# MiddleMotor.net
KiCad netlist of a schematic drawn in EasyEDA Pro
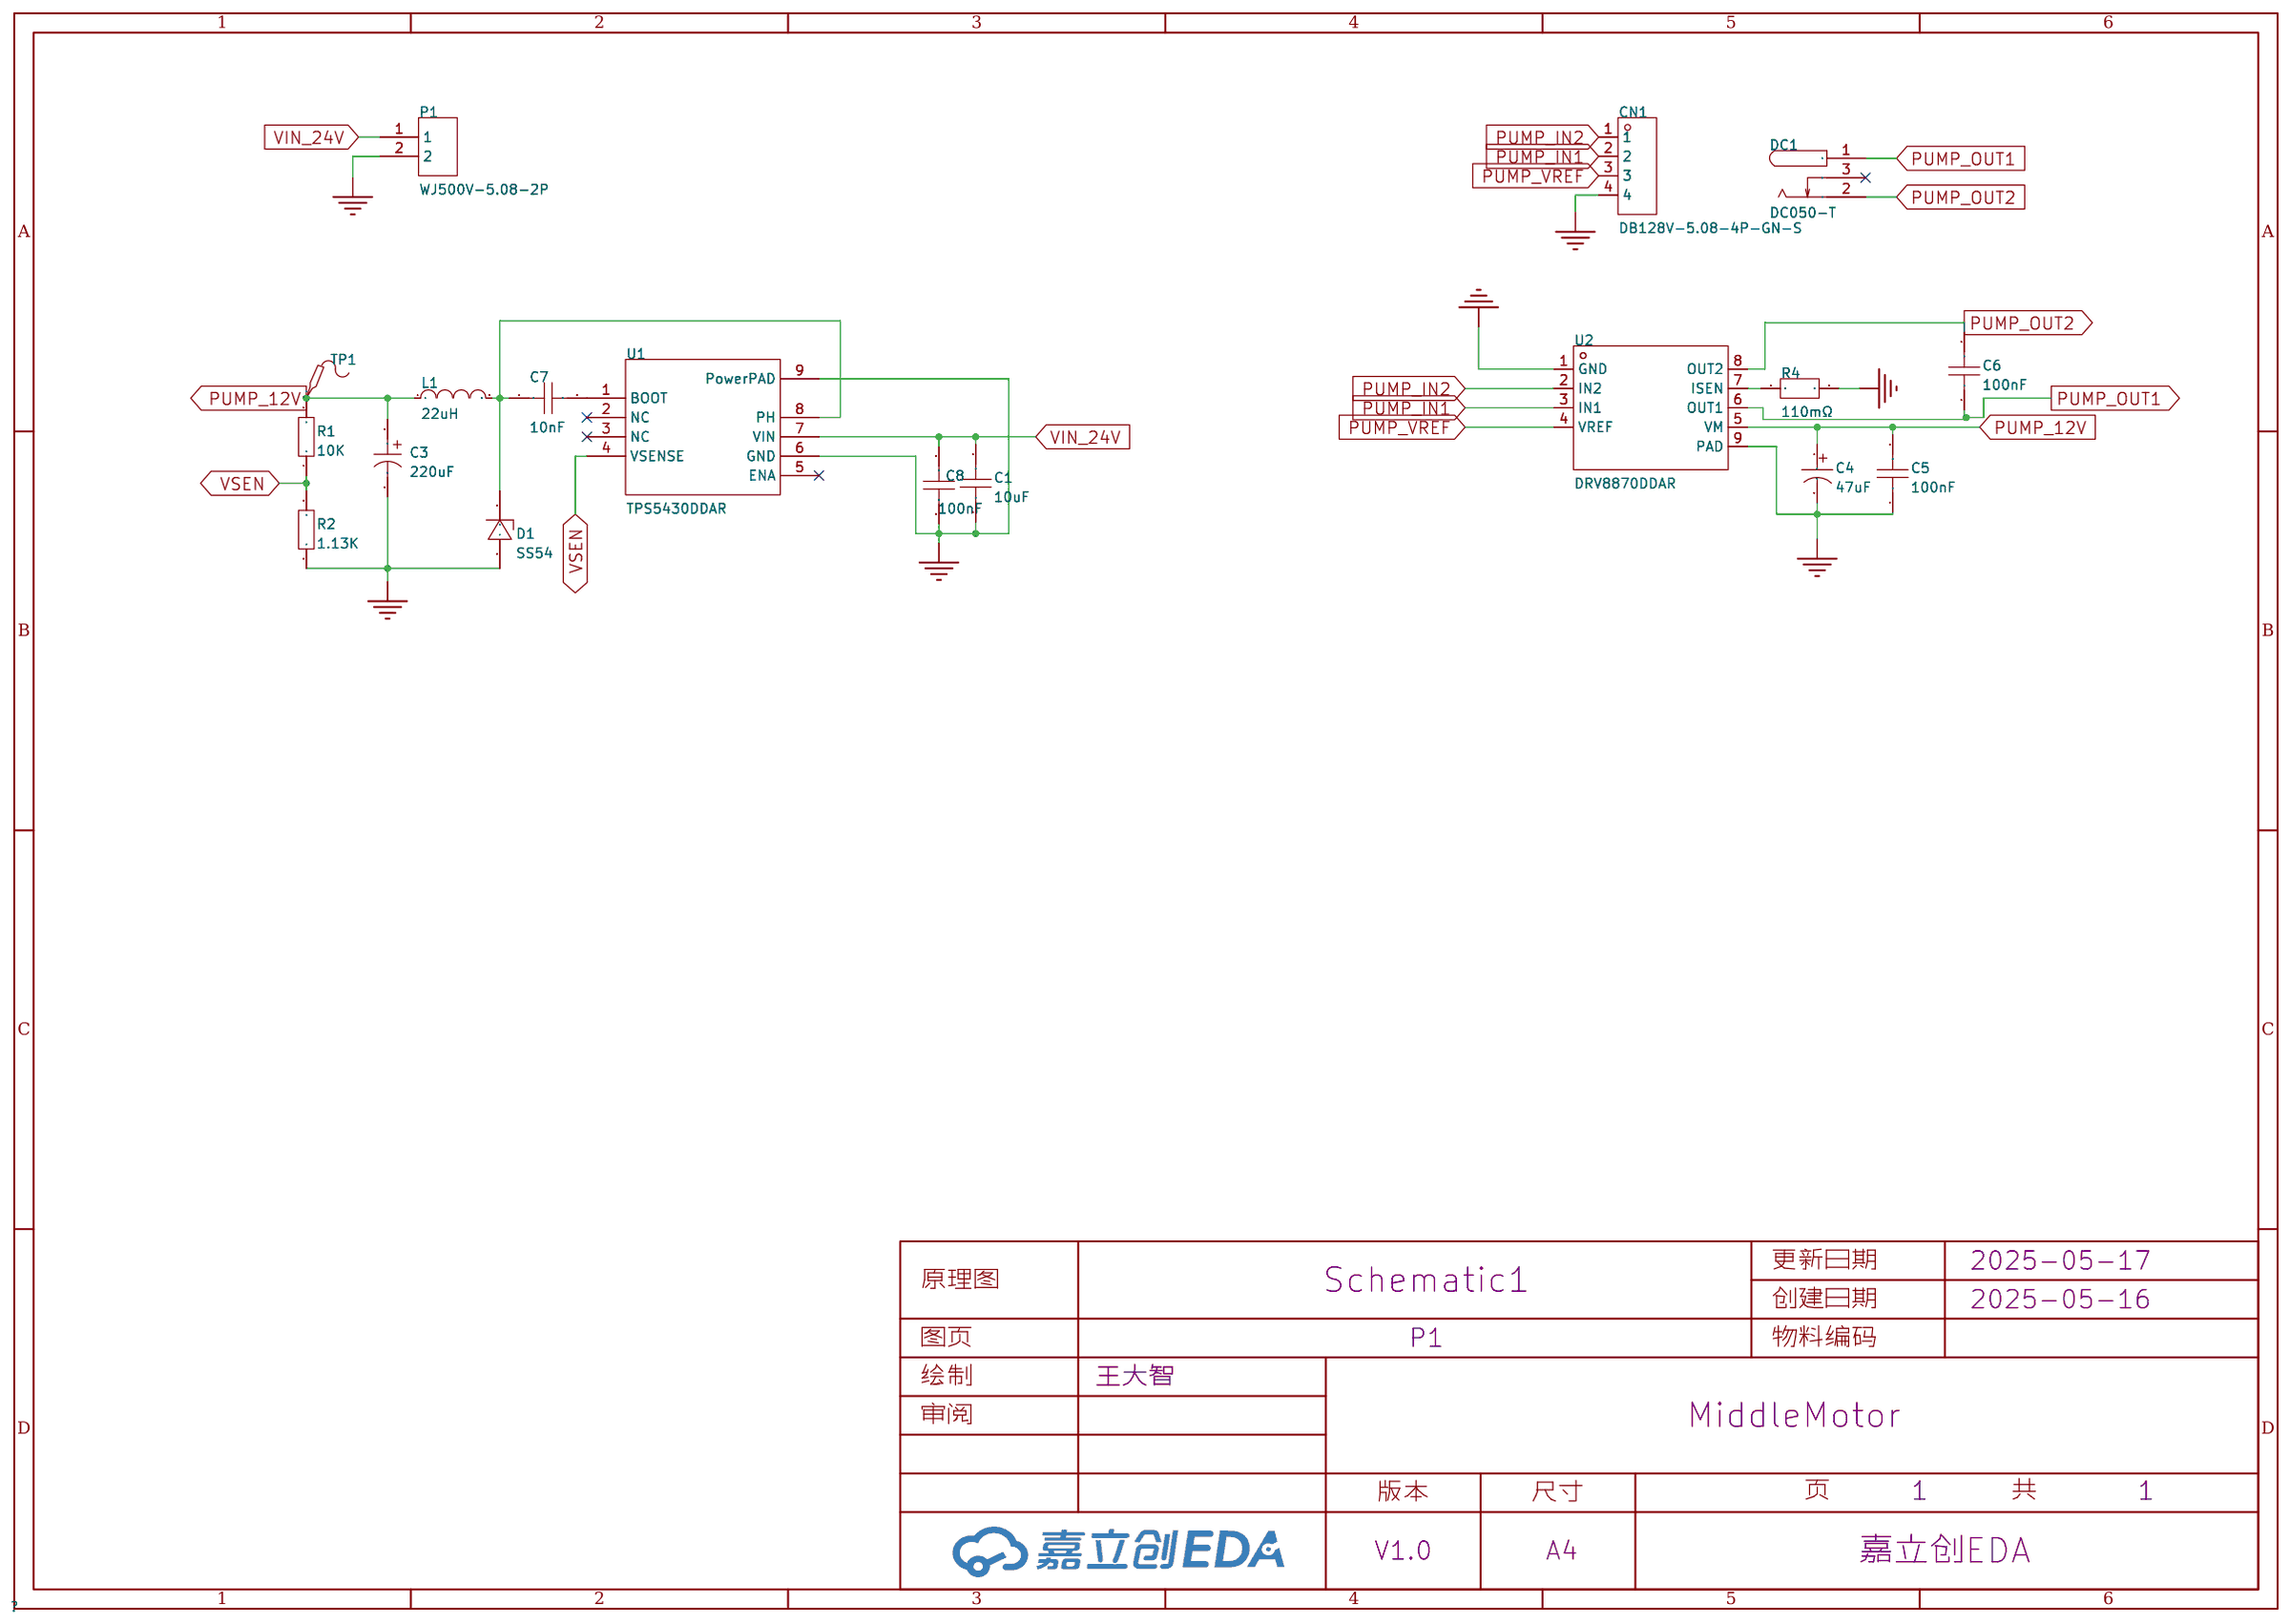
[diagram p0: schematic sheet]

(export (version "E")
  (design (tool "Eeschema 10.0.6"))
  (components
    (comp (ref "C1")
      (value "10uF")
      (footprint "easyedapro:C1206")
      (description "容值:10uF;精度:±10%;额定电压:50V;温度系数:X5R;")
      (fields
        (field (name "Manufacturer Part") "HGC1206R5106K500NSPJ")
        (field (name "Manufacturer") "Chinocera(华瓷)")
      )
      (libsource (lib "easyedapro") (part "HGC1206R5106K500NSPJ"))
    )
    (comp (ref "C3")
      (value "220uF")
      (footprint "easyedapro:CAP-SMD_BD8.0-L8.3-W8.3-FD")
      (description "容值:220uF;精度:±20%;额定电压:35V;纹波电流:175mA@120Hz;")
      (fields
        (field (name "Manufacturer Part") "GVT1V227M0810CNVC")
        (field (name "Manufacturer") "HRK(鸿瑞凯电子)")
      )
      (libsource (lib "easyedapro") (part "GVT1V227M0810CNVC"))
    )
    (comp (ref "C4")
      (value "47uF")
      (footprint "easyedapro:CAP-TH_BD6.3-P2.50-D1.0-FD")
      (description "容值:47uF;精度:±20%;额定电压:50V;")
      (fields
        (field (name "Manufacturer Part") "KM476M050E11RR0VH2FP0")
        (field (name "Manufacturer") "CX(承兴)")
      )
      (libsource (lib "easyedapro") (part "47uF 50V 6.3*11_C45101"))
    )
    (comp (ref "C5")
      (value "100nF")
      (footprint "easyedapro:C0603")
      (description "容值:100nF;精度:±10%;额定电压:50V;温度系数:X7R;")
      (fields
        (field (name "Manufacturer Part") "CGA0603X7R104K500JT")
        (field (name "Manufacturer") "HRE(芯声)")
      )
      (libsource (lib "easyedapro") (part "CGA0603X7R104K500JT"))
    )
    (comp (ref "C6")
      (value "100nF")
      (footprint "easyedapro:C0603")
      (description "容值:100nF;精度:±10%;额定电压:50V;温度系数:X7R;")
      (fields
        (field (name "Manufacturer Part") "CGA0603X7R104K500JT")
        (field (name "Manufacturer") "HRE(芯声)")
      )
      (libsource (lib "easyedapro") (part "CGA0603X7R104K500JT"))
    )
    (comp (ref "C7")
      (value "10nF")
      (footprint "easyedapro:C0603")
      (libsource (lib "easyedapro") (part "CapAcitance"))
    )
    (comp (ref "C8")
      (value "100nF")
      (footprint "easyedapro:C0603")
      (libsource (lib "easyedapro") (part "CapAcitance"))
    )
    (comp (ref "CN1")
      (value "DB128V-5.08-4P-GN-S")
      (footprint "easyedapro:CONN-TH_4P-P5.08_DIBO_DB128V-5.08")
      (fields (field (name "Manufacturer") "DORABO(地博电气)"))
      (libsource (lib "easyedapro") (part "DB128V-5.08-4P-GN-S"))
    )
    (comp (ref "D1")
      (value "SS54")
      (footprint "easyedapro:SMA_L4.3-W2.6-LS5.0-FD")
      (description "二极管配置:独立式;正向压降(Vf):550mV@5.0A;直流反向耐压(Vr):40V;整流电流:5A;")
      (fields (field (name "Manufacturer") "宏迦橙"))
      (libsource (lib "easyedapro") (part "SS54_C7420369"))
    )
    (comp (ref "DC1")
      (value "DC050-T")
      (footprint "easyedapro:DC-IN_DC050-T")
      (description "连接器类型:DC电源插座;安装方式:卧贴;触点内径:2mm;触点外径:6.4mm;额定电流:2A;额定电压:30V;工作温度范围:-25°C~+70°C;")
      (fields (field (name "Manufacturer") "SHOU HAN(首韩)"))
      (libsource (lib "easyedapro") (part "DC050-T"))
    )
    (comp (ref "L1")
      (value "22uH")
      (footprint "easyedapro:IND-SMD_L7.0-W6.6_FXL0630")
      (description "电感值:22uH;精度:±20%;额定电流:2.5A;饱和电流(Isat):3A;类型:一体成型电感;")
      (fields (field (name "Manufacturer Part") "FXL0630-220-M") (field (name "Manufacturer") "cjiang(长江微电)"))
      (libsource (lib "easyedapro") (part "FXL0630-220-M"))
    )
    (comp (ref "P1")
      (value "WJ500V-5.08-2P")
      (footprint "easyedapro:CONN-TH_2P-P5.00_WJ500V-5.08-2P")
      (fields (field (name "Manufacturer") "KANGNEX(康奈克斯电气)"))
      (libsource (lib "easyedapro") (part "WJ500V-5.08-2P-14-00A"))
    )
    (comp (ref "R1") (value "10K") (footprint "easyedapro:R0603") (libsource (lib "easyedapro") (part "电阻")))
    (comp (ref "R2")
      (value "1.13K")
      (footprint "easyedapro:R0603")
      (libsource (lib "easyedapro") (part "电阻"))
    )
    (comp (ref "R4")
      (value "110mΩ")
      (footprint "easyedapro:R1206")
      (description "电阻类型:厚膜电阻;阻值:110mΩ;精度:±1%;功率:250mW;最大工作电压:500V;温度系数:±600ppm/°C;")
      (fields (field (name "Manufacturer Part") "FRL1206FR110TS") (field (name "Manufacturer") "FOJAN(富捷)"))
      (libsource (lib "easyedapro") (part "FRL1206FR110TS"))
    )
    (comp (ref "TP1")
      (value "~")
      (footprint "easyedapro:Test-Point-0.5mm")
      (description "Test Point 测试点")
      (libsource (lib "easyedapro") (part "Test-Point"))
    )
    (comp (ref "U1")
      (value "TPS5430DDAR")
      (footprint "easyedapro:ESOP-8_L4.9-W3.9-P1.27-LS6.0-TL-EP")
      (description "功能类型:降压型;输出类型:可调;工作电压:5.5V~36V;输出电压:1.221V~32.04V;输出电流:3A;")
      (fields (field (name "Manufacturer") "TI(德州仪器)"))
      (libsource (lib "easyedapro") (part "TPS5430DDAR"))
    )
    (comp (ref "U2")
      (value "DRV8870DDAR")
      (footprint "easyedapro:HSOP-8_L5.0-W4.0-P1.27-LS6.2-BL-EP")
      (description "DRV8870 具有电流调节功能的 50V、3.6A、H 桥电机驱动器")
      (fields (field (name "Manufacturer") "TI(德州仪器)"))
      (libsource (lib "easyedapro") (part "DRV8870DDAR"))
    )
  )
  (nets
    (net (code "1") (name "GND") (class "Default")
      (node (ref "C1") (pin "1") (pinfunction "1_1") (pintype "unspecified"))
      (node (ref "C3") (pin "2") (pinfunction "2_2") (pintype "input"))
      (node (ref "C4") (pin "2") (pinfunction "2_2") (pintype "input"))
      (node (ref "C5") (pin "1") (pinfunction "1_1") (pintype "unspecified"))
      (node (ref "C8") (pin "2") (pinfunction "2_2") (pintype "input"))
      (node (ref "CN1") (pin "4") (pinfunction "4_4") (pintype "unspecified"))
      (node (ref "D1") (pin "1") (pinfunction "A_1") (pintype "unspecified"))
      (node (ref "P1") (pin "2") (pinfunction "2_2") (pintype "unspecified"))
      (node (ref "R2") (pin "1") (pinfunction "1_1") (pintype "input"))
      (node (ref "R4") (pin "2") (pinfunction "2_2") (pintype "unspecified"))
      (node (ref "U1") (pin "6") (pinfunction "GND_6") (pintype "unspecified"))
      (node (ref "U1") (pin "9") (pinfunction "PowerPAD_9") (pintype "unspecified"))
      (node (ref "U2") (pin "1") (pinfunction "GND_1") (pintype "unspecified"))
      (node (ref "U2") (pin "9") (pinfunction "PAD_9") (pintype "unspecified"))
    )
    (net (code "2") (name "Net-(D1-K)") (class "Default")
      (node (ref "C7") (pin "1") (pinfunction "1_1") (pintype "input"))
      (node (ref "D1") (pin "2") (pinfunction "K_2") (pintype "unspecified"))
      (node (ref "L1") (pin "2") (pinfunction "2_2") (pintype "unspecified"))
      (node (ref "U1") (pin "8") (pinfunction "PH_8") (pintype "unspecified"))
    )
    (net (code "3") (name "Net-(U1-BOOT)") (class "Default")
      (node (ref "C7") (pin "2") (pinfunction "2_2") (pintype "input"))
      (node (ref "U1") (pin "1") (pinfunction "BOOT_1") (pintype "unspecified"))
    )
    (net (code "4") (name "Net-(U2-ISEN)") (class "Default")
      (node (ref "R4") (pin "1") (pinfunction "1_1") (pintype "unspecified"))
      (node (ref "U2") (pin "7") (pinfunction "ISEN_7") (pintype "unspecified"))
    )
    (net (code "5") (name "PUMP_12V") (class "Default")
      (node (ref "C3") (pin "1") (pinfunction "1_1") (pintype "input"))
      (node (ref "C4") (pin "1") (pinfunction "1_1") (pintype "input"))
      (node (ref "C5") (pin "2") (pinfunction "2_2") (pintype "unspecified"))
      (node (ref "L1") (pin "1") (pinfunction "1_1") (pintype "unspecified"))
      (node (ref "R1") (pin "2") (pinfunction "2_2") (pintype "input"))
      (node (ref "TP1") (pin "1") (pinfunction "1_1") (pintype "input"))
      (node (ref "U2") (pin "5") (pinfunction "VM_5") (pintype "unspecified"))
    )
    (net (code "6") (name "PUMP_IN1") (class "Default")
      (node (ref "CN1") (pin "2") (pinfunction "2_2") (pintype "unspecified"))
      (node (ref "U2") (pin "3") (pinfunction "IN1_3") (pintype "unspecified"))
    )
    (net (code "7") (name "PUMP_IN2") (class "Default")
      (node (ref "CN1") (pin "1") (pinfunction "1_1") (pintype "unspecified"))
      (node (ref "U2") (pin "2") (pinfunction "IN2_2") (pintype "unspecified"))
    )
    (net (code "8") (name "PUMP_OUT1") (class "Default")
      (node (ref "C6") (pin "1") (pinfunction "1_1") (pintype "unspecified"))
      (node (ref "DC1") (pin "1") (pinfunction "1_1") (pintype "unspecified"))
      (node (ref "U2") (pin "6") (pinfunction "OUT1_6") (pintype "unspecified"))
    )
    (net (code "9") (name "PUMP_OUT2") (class "Default")
      (node (ref "C6") (pin "2") (pinfunction "2_2") (pintype "unspecified"))
      (node (ref "DC1") (pin "2") (pinfunction "2_2") (pintype "unspecified"))
      (node (ref "U2") (pin "8") (pinfunction "OUT2_8") (pintype "unspecified"))
    )
    (net (code "10") (name "PUMP_VREF") (class "Default")
      (node (ref "CN1") (pin "3") (pinfunction "3_3") (pintype "unspecified"))
      (node (ref "U2") (pin "4") (pinfunction "VREF_4") (pintype "unspecified"))
    )
    (net (code "11") (name "VIN_24V") (class "Default")
      (node (ref "C1") (pin "2") (pinfunction "2_2") (pintype "unspecified"))
      (node (ref "C8") (pin "1") (pinfunction "1_1") (pintype "input"))
      (node (ref "P1") (pin "1") (pinfunction "1_1") (pintype "unspecified"))
      (node (ref "U1") (pin "7") (pinfunction "VIN_7") (pintype "unspecified"))
    )
    (net (code "12") (name "VSEN") (class "Default")
      (node (ref "R1") (pin "1") (pinfunction "1_1") (pintype "input"))
      (node (ref "R2") (pin "2") (pinfunction "2_2") (pintype "input"))
      (node (ref "U1") (pin "4") (pinfunction "VSENSE_4") (pintype "unspecified"))
    )
    (net (code "13") (name "unconnected-(DC1-Pad3)") (class "Default")
      (node (ref "DC1") (pin "3") (pinfunction "3_3") (pintype "unspecified+no_connect"))
    )
    (net (code "14") (name "unconnected-(U1-ENA-Pad5)") (class "Default")
      (node (ref "U1") (pin "5") (pinfunction "ENA_5") (pintype "unspecified+no_connect"))
    )
    (net (code "15") (name "unconnected-(U1-NC-Pad2)") (class "Default")
      (node (ref "U1") (pin "2") (pinfunction "NC_2") (pintype "unspecified+no_connect"))
    )
    (net (code "16") (name "unconnected-(U1-NC-Pad3)") (class "Default")
      (node (ref "U1") (pin "3") (pinfunction "NC_3") (pintype "unspecified+no_connect"))
    )
  )
)
